# motherboard_conectors.net
KiCad netlist of a schematic drawn in Altium Designer
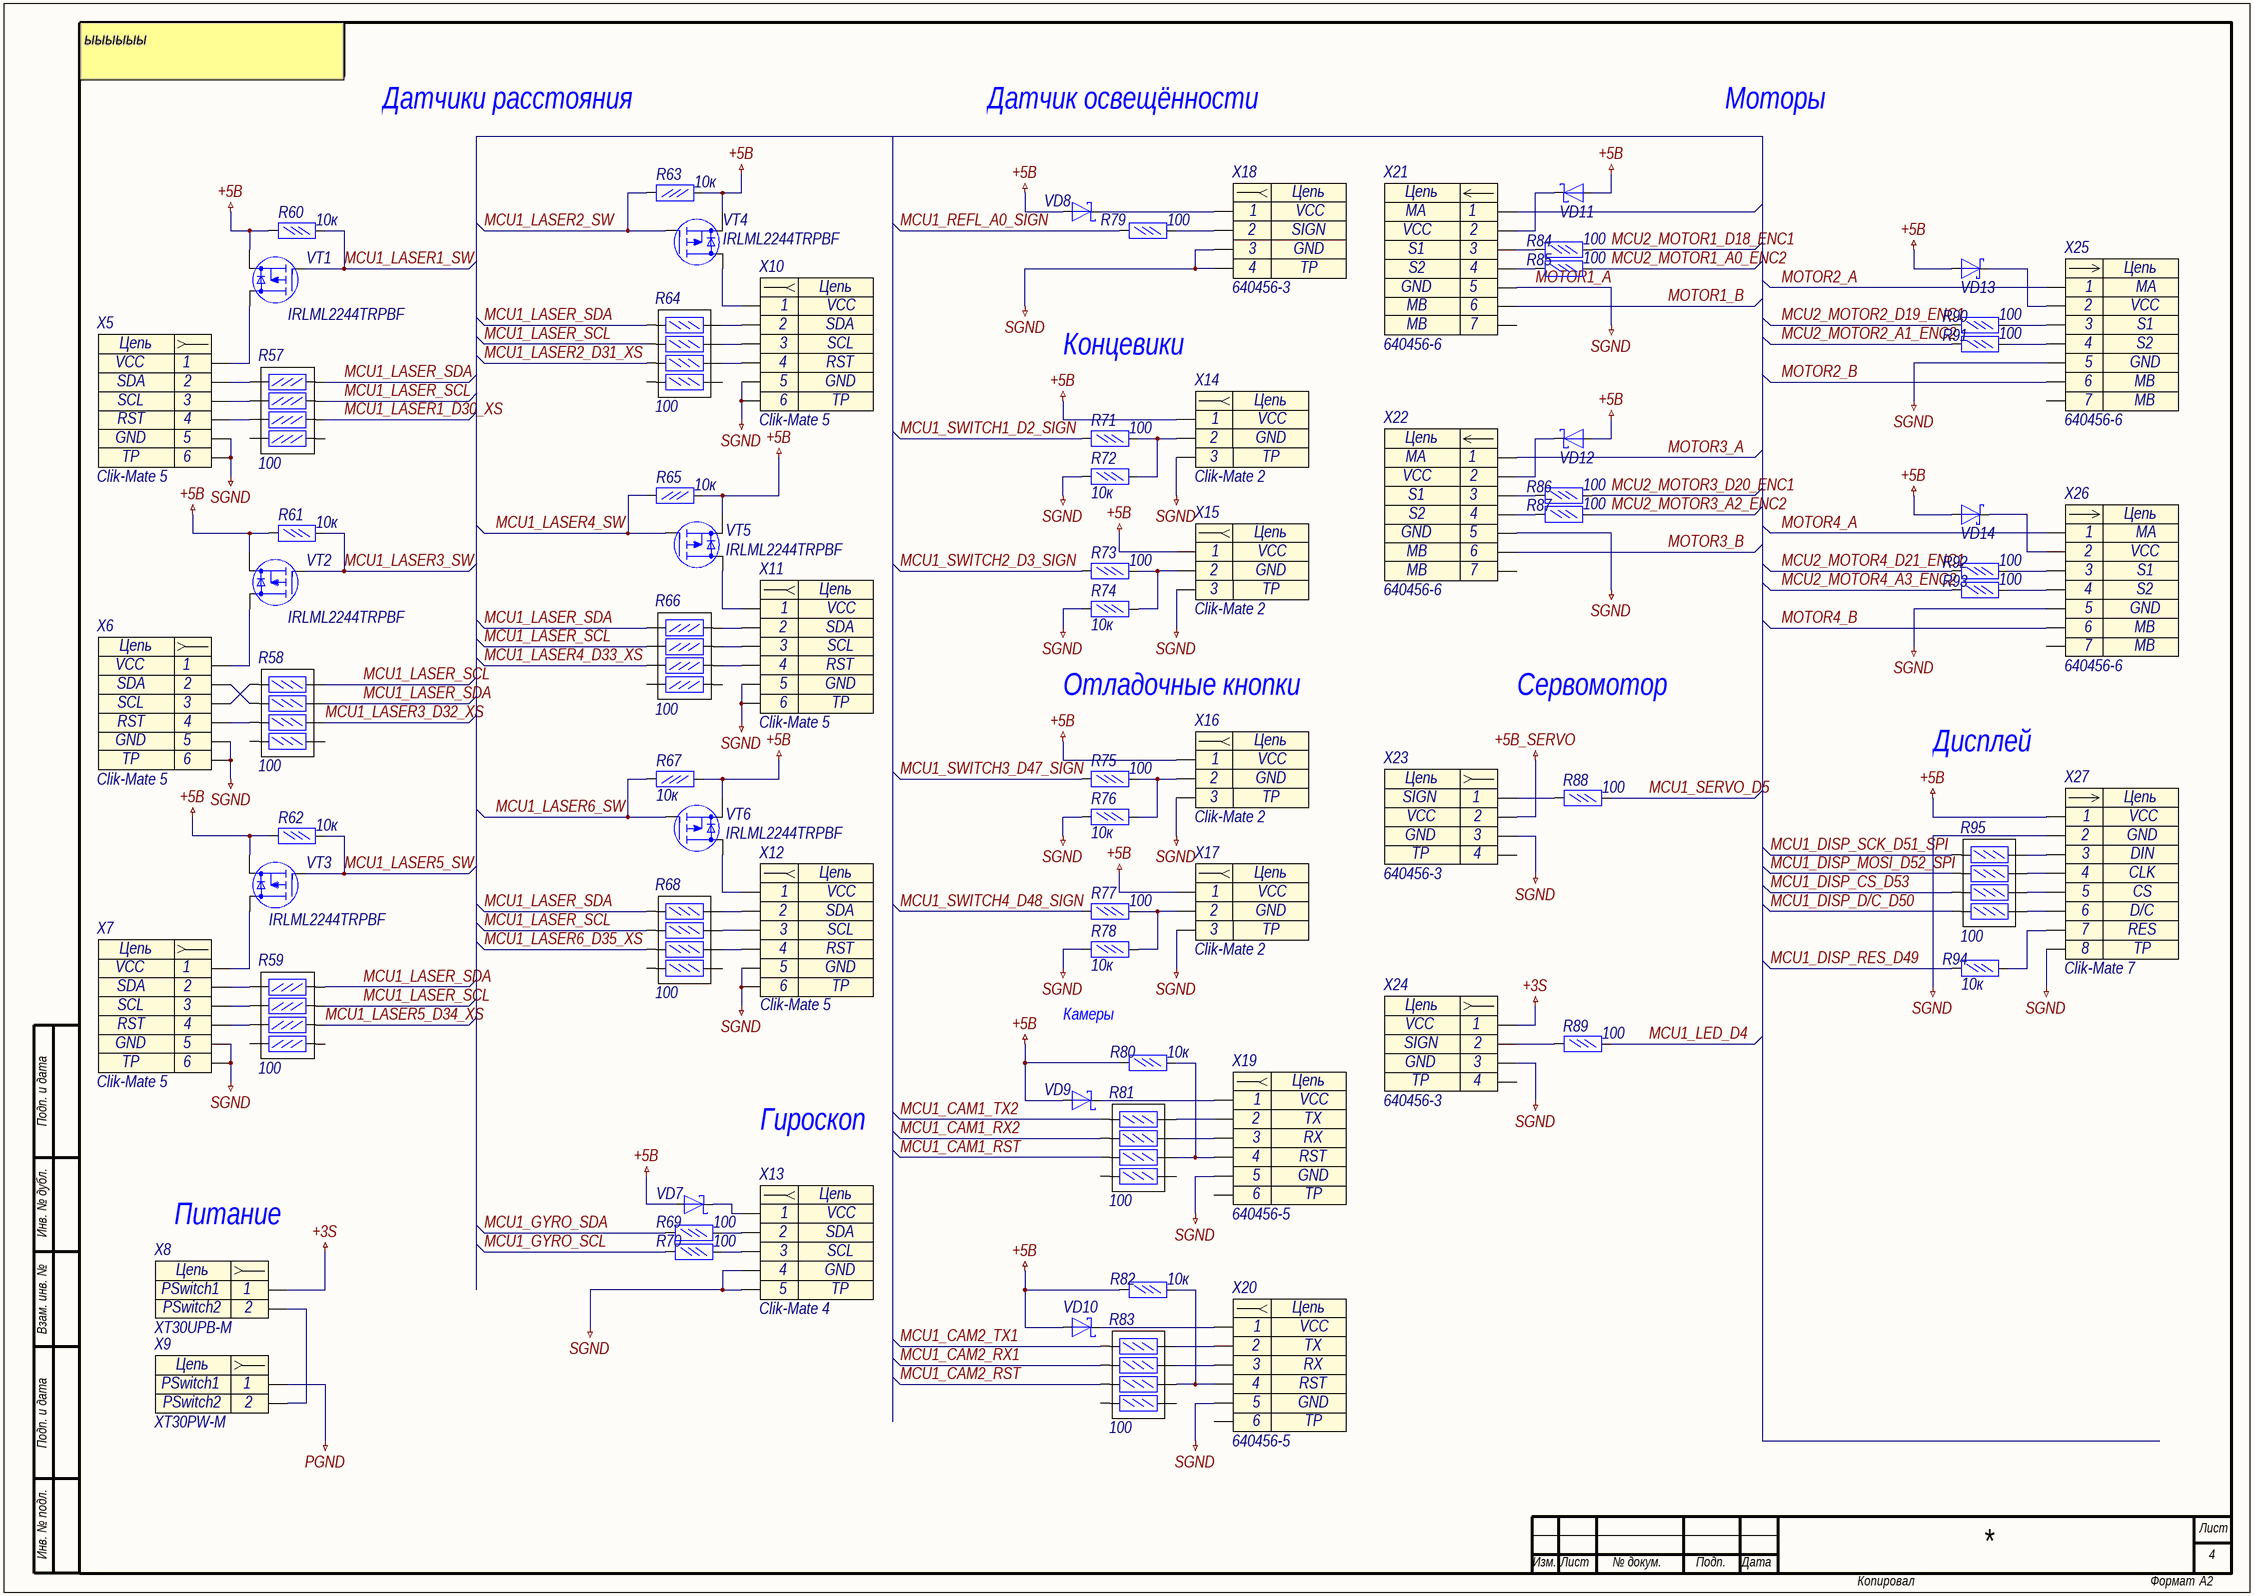
[diagram p0: motherboard_conectors.SchDoc]

(export (version "E")
  (design (tool "Eeschema 10.0.6"))
  (components
    (comp (ref "R57")
      (value "100")
      (footprint "R0603X4")
      (libsource (lib "") (part "Резисторная сборка 0.05 x 4_1"))
    )
    (comp (ref "R58")
      (value "100")
      (footprint "R0603X4")
      (libsource (lib "mylib") (part "Резисторная сборка 0.05 x 4"))
    )
    (comp (ref "R59")
      (value "100")
      (footprint "R0603X4")
      (libsource (lib "") (part "Резисторная сборка 0.05 x 4_1"))
    )
    (comp (ref "R60")
      (value "10к")
      (footprint "R0603")
      (description "Резистор 0,05Вт")
      (libsource (lib "mylib") (part "Резистор 0.05Вт"))
    )
    (comp (ref "R61")
      (value "10к")
      (footprint "R0603")
      (description "Резистор 0,05Вт")
      (libsource (lib "mylib") (part "Резистор 0.05Вт"))
    )
    (comp (ref "R62")
      (value "10к")
      (footprint "R0603")
      (description "Резистор 0,05Вт")
      (libsource (lib "mylib") (part "Резистор 0.05Вт"))
    )
    (comp (ref "R63")
      (value "10к")
      (footprint "R0603")
      (description "Резистор 0,05Вт")
      (libsource (lib "") (part "Резистор  0,05Вт_1"))
    )
    (comp (ref "R64")
      (value "100")
      (footprint "R0603X4")
      (libsource (lib "mylib") (part "Резисторная сборка 0.05 x 4"))
    )
    (comp (ref "R65")
      (value "10к")
      (footprint "R0603")
      (description "Резистор 0,05Вт")
      (libsource (lib "") (part "Резистор  0,05Вт_1"))
    )
    (comp (ref "R66")
      (value "100")
      (footprint "R0603X4")
      (libsource (lib "") (part "Резисторная сборка 0.05 x 4_1"))
    )
    (comp (ref "R67")
      (value "10к")
      (footprint "R0603")
      (description "Резистор 0,05Вт")
      (libsource (lib "") (part "Резистор  0,05Вт_1"))
    )
    (comp (ref "R68")
      (value "100")
      (footprint "R0603X4")
      (libsource (lib "mylib") (part "Резисторная сборка 0.05 x 4"))
    )
    (comp (ref "R69")
      (value "100")
      (footprint "R0603")
      (description "Резистор 0,05Вт")
      (libsource (lib "mylib") (part "Резистор 0.05Вт"))
    )
    (comp (ref "R70")
      (value "100")
      (footprint "R0603")
      (description "Резистор 0,05Вт")
      (libsource (lib "mylib") (part "Резистор 0.05Вт"))
    )
    (comp (ref "R71")
      (value "100")
      (footprint "R0603")
      (description "Резистор 0,05Вт")
      (libsource (lib "mylib") (part "Резистор  0,05Вт"))
    )
    (comp (ref "R72")
      (value "10к")
      (footprint "R0603")
      (description "Резистор 0,05Вт")
      (libsource (lib "mylib") (part "Резистор  0,05Вт"))
    )
    (comp (ref "R73")
      (value "100")
      (footprint "R0603")
      (description "Резистор 0,05Вт")
      (libsource (lib "mylib") (part "Резистор  0,05Вт"))
    )
    (comp (ref "R74")
      (value "10к")
      (footprint "R0603")
      (description "Резистор 0,05Вт")
      (libsource (lib "mylib") (part "Резистор  0,05Вт"))
    )
    (comp (ref "R75")
      (value "100")
      (footprint "R0603")
      (description "Резистор 0,05Вт")
      (libsource (lib "mylib") (part "Резистор  0,05Вт"))
    )
    (comp (ref "R76")
      (value "10к")
      (footprint "R0603")
      (description "Резистор 0,05Вт")
      (libsource (lib "mylib") (part "Резистор  0,05Вт"))
    )
    (comp (ref "R77")
      (value "100")
      (footprint "R0603")
      (description "Резистор 0,05Вт")
      (libsource (lib "mylib") (part "Резистор  0,05Вт"))
    )
    (comp (ref "R78")
      (value "10к")
      (footprint "R0603")
      (description "Резистор 0,05Вт")
      (libsource (lib "mylib") (part "Резистор  0,05Вт"))
    )
    (comp (ref "R79")
      (value "100")
      (footprint "R0603")
      (description "Резистор 0,05Вт")
      (libsource (lib "mylib") (part "Резистор  0,05Вт"))
    )
    (comp (ref "R80")
      (value "10к")
      (footprint "R0603")
      (description "Резистор 0,05Вт")
      (libsource (lib "mylib") (part "Резистор 0.05Вт"))
    )
    (comp (ref "R81")
      (value "100")
      (footprint "R0603X4")
      (libsource (lib "mylib") (part "Резисторная сборка 0.05 x 4"))
    )
    (comp (ref "R82")
      (value "10к")
      (footprint "R0603")
      (description "Резистор 0,05Вт")
      (libsource (lib "mylib") (part "Резистор 0.05Вт"))
    )
    (comp (ref "R83")
      (value "100")
      (footprint "R0603X4")
      (libsource (lib "mylib") (part "Резисторная сборка 0.05 x 4"))
    )
    (comp (ref "R84")
      (value "100")
      (footprint "R0603")
      (description "Резистор 0,05Вт")
      (libsource (lib "mylib") (part "Резистор  0,05Вт"))
    )
    (comp (ref "R85")
      (value "100")
      (footprint "R0603")
      (description "Резистор 0,05Вт")
      (libsource (lib "mylib") (part "Резистор  0,05Вт"))
    )
    (comp (ref "R86")
      (value "100")
      (footprint "R0603")
      (description "Резистор 0,05Вт")
      (libsource (lib "mylib") (part "Резистор  0,05Вт"))
    )
    (comp (ref "R87")
      (value "100")
      (footprint "R0603")
      (description "Резистор 0,05Вт")
      (libsource (lib "mylib") (part "Резистор  0,05Вт"))
    )
    (comp (ref "R88")
      (value "100")
      (footprint "R0603")
      (description "Резистор 0,05Вт")
      (libsource (lib "mylib") (part "Резистор  0,05Вт"))
    )
    (comp (ref "R89")
      (value "100")
      (footprint "R0603")
      (description "Резистор 0,05Вт")
      (libsource (lib "mylib") (part "Резистор  0,05Вт"))
    )
    (comp (ref "R90")
      (value "100")
      (footprint "R0603")
      (description "Резистор 0,05Вт")
      (libsource (lib "mylib") (part "Резистор  0,05Вт"))
    )
    (comp (ref "R91")
      (value "100")
      (footprint "R0603")
      (description "Резистор 0,05Вт")
      (libsource (lib "mylib") (part "Резистор  0,05Вт"))
    )
    (comp (ref "R92")
      (value "100")
      (footprint "R0603")
      (description "Резистор 0,05Вт")
      (libsource (lib "mylib") (part "Резистор  0,05Вт"))
    )
    (comp (ref "R93")
      (value "100")
      (footprint "R0603")
      (description "Резистор 0,05Вт")
      (libsource (lib "mylib") (part "Резистор  0,05Вт"))
    )
    (comp (ref "R94")
      (value "10к")
      (footprint "R0603")
      (description "Резистор 0,05Вт")
      (libsource (lib "mylib") (part "Резистор  0,05Вт"))
    )
    (comp (ref "R95")
      (value "100")
      (footprint "R0603X4")
      (libsource (lib "mylib") (part "Резисторная сборка 0.05 x 4"))
    )
    (comp (ref "VD7")
      (value "~")
      (footprint "SOD123_A")
      (description "Диод Шоттки")
      (libsource (lib "mylib") (part "DiodeSchottky"))
    )
    (comp (ref "VD8")
      (value "~")
      (footprint "SOD123_A")
      (description "Диод Шоттки")
      (libsource (lib "mylib") (part "DiodeSchottky"))
    )
    (comp (ref "VD9")
      (value "~")
      (footprint "SOD123_A")
      (description "Диод Шоттки")
      (libsource (lib "mylib") (part "DiodeSchottky"))
    )
    (comp (ref "VD10")
      (value "~")
      (footprint "SOD123_A")
      (description "Диод Шоттки")
      (libsource (lib "mylib") (part "DiodeSchottky"))
    )
    (comp (ref "VD11")
      (value "~")
      (footprint "SOD123_A")
      (description "Диод Шоттки")
      (libsource (lib "mylib") (part "DiodeSchottky"))
    )
    (comp (ref "VD12")
      (value "~")
      (footprint "SOD123_A")
      (description "Диод Шоттки")
      (libsource (lib "mylib") (part "DiodeSchottky"))
    )
    (comp (ref "VD13")
      (value "~")
      (footprint "SOD123_A")
      (description "Диод Шоттки")
      (libsource (lib "mylib") (part "DiodeSchottky"))
    )
    (comp (ref "VD14")
      (value "~")
      (footprint "SOD123_A")
      (description "Диод Шоттки")
      (libsource (lib "mylib") (part "DiodeSchottky"))
    )
    (comp (ref "VT1")
      (value "IRLML2244TRPBF")
      (footprint "SOT23")
      (libsource (lib "mylib") (part "транзистор n-канал"))
    )
    (comp (ref "VT2")
      (value "IRLML2244TRPBF")
      (footprint "SOT23")
      (libsource (lib "mylib") (part "транзистор n-канал"))
    )
    (comp (ref "VT3")
      (value "IRLML2244TRPBF")
      (footprint "SOT23")
      (libsource (lib "mylib") (part "транзистор n-канал"))
    )
    (comp (ref "VT4")
      (value "IRLML2244TRPBF")
      (footprint "SOT23")
      (libsource (lib "mylib") (part "транзистор n-канал"))
    )
    (comp (ref "VT5")
      (value "IRLML2244TRPBF")
      (footprint "SOT23")
      (libsource (lib "mylib") (part "транзистор n-канал"))
    )
    (comp (ref "VT6")
      (value "IRLML2244TRPBF")
      (footprint "SOT23")
      (libsource (lib "mylib") (part "транзистор n-канал"))
    )
    (comp (ref "X5")
      (value "Clik-Mate 5")
      (footprint "Clik-Mate 5")
      (description "Разъем - 5 конт. мама")
      (libsource (lib "") (part "Header_5_1"))
    )
    (comp (ref "X6")
      (value "Clik-Mate 5")
      (footprint "Clik-Mate 5")
      (description "Разъем - 5 конт. мама")
      (libsource (lib "") (part "Header_5_1"))
    )
    (comp (ref "X7")
      (value "Clik-Mate 5")
      (footprint "Clik-Mate 5")
      (description "Разъем - 5 конт. мама")
      (libsource (lib "") (part "Header_5_1"))
    )
    (comp (ref "X8") (value "XT30UPB-M") (footprint "XT30UPB-M") (libsource (lib "mylib") (part "XT30UPB-M")))
    (comp (ref "X9") (value "XT30PW-M") (footprint "XT30PW-M") (libsource (lib "mylib") (part "XT30PW-M")))
    (comp (ref "X10")
      (value "Clik-Mate 5")
      (footprint "Clik-Mate 5")
      (description "Разъем - 5 конт. мама")
      (libsource (lib "mylib") (part "Header_5"))
    )
    (comp (ref "X11")
      (value "Clik-Mate 5")
      (footprint "Clik-Mate 5")
      (description "Разъем - 5 конт. мама")
      (libsource (lib "mylib") (part "Header_5"))
    )
    (comp (ref "X12")
      (value "Clik-Mate 5")
      (footprint "Clik-Mate 5")
      (description "Разъем - 5 конт. мама")
      (libsource (lib "mylib") (part "Header_5"))
    )
    (comp (ref "X13")
      (value "Clik-Mate 4")
      (footprint "Clik-Mate 4")
      (description "Разъем - 4 конт. мама")
      (libsource (lib "mylib") (part "Header_4"))
    )
    (comp (ref "X14")
      (value "Clik-Mate 2")
      (footprint "Clik-Mate 2")
      (description "Разъем - 3 конт. розетка")
      (libsource (lib "mylib") (part "Header_2"))
    )
    (comp (ref "X15")
      (value "Clik-Mate 2")
      (footprint "Clik-Mate 2")
      (description "Разъем - 3 конт. розетка")
      (libsource (lib "mylib") (part "Header_2"))
    )
    (comp (ref "X16")
      (value "Clik-Mate 2")
      (footprint "Clik-Mate 2")
      (description "Разъем - 3 конт. розетка")
      (libsource (lib "mylib") (part "Header_2"))
    )
    (comp (ref "X17")
      (value "Clik-Mate 2")
      (footprint "Clik-Mate 2")
      (description "Разъем - 3 конт. розетка")
      (libsource (lib "mylib") (part "Header_2"))
    )
    (comp (ref "X18")
      (value "640456-3")
      (footprint "Clik-Mate 3")
      (description "Разъем - 3 конт. розетка")
      (libsource (lib "") (part "Header_3_1"))
    )
    (comp (ref "X19")
      (value "640456-5")
      (footprint "JST-640456-5")
      (description "Разъем - 5 конт. мама")
      (libsource (lib "mylib") (part "Header_5"))
    )
    (comp (ref "X20")
      (value "640456-5")
      (footprint "JST-640456-5")
      (description "Разъем - 5 конт. мама")
      (libsource (lib "mylib") (part "Header_5"))
    )
    (comp (ref "X21")
      (value "640456-6")
      (footprint "JST-640456-6")
      (description "Разъем - 6 конт. мама")
      (libsource (lib "") (part "Header_6_1"))
    )
    (comp (ref "X22")
      (value "640456-6")
      (footprint "JST-640456-6")
      (description "Разъем - 6 конт. мама")
      (libsource (lib "") (part "Header_6_1"))
    )
    (comp (ref "X23")
      (value "640456-3")
      (footprint "JST-640456-3")
      (description "Разъем - 3 конт. розетка")
      (libsource (lib "mylib") (part "Header_3"))
    )
    (comp (ref "X24")
      (value "640456-3")
      (footprint "JST-640456-3")
      (description "Разъем - 3 конт. розетка")
      (libsource (lib "mylib") (part "Header_3"))
    )
    (comp (ref "X25")
      (value "640456-6")
      (footprint "JST-640456-6")
      (description "Разъем - 6 конт. мама")
      (libsource (lib "mylib") (part "Header_6"))
    )
    (comp (ref "X26")
      (value "640456-6")
      (footprint "JST-640456-6")
      (description "Разъем - 6 конт. мама")
      (libsource (lib "mylib") (part "Header_6"))
    )
    (comp (ref "X27")
      (value "Clik-Mate 7")
      (footprint "Clik-Mate 7")
      (description "Разъем - 7 конт. мама")
      (libsource (lib "mylib") (part "Header_7"))
    )
  )
  (nets
    (net (code "1") (name "+3S") (class "Default")
      (node (ref "X24") (pin "1") (pinfunction "1_1") (pintype "passive"))
      (node (ref "X8") (pin "1") (pinfunction "1_1") (pintype "passive"))
    )
    (net (code "2") (name "+5В") (class "Default")
      (node (ref "R60") (pin "1") (pinfunction "1_1") (pintype "passive"))
      (node (ref "R61") (pin "1") (pinfunction "1_1") (pintype "passive"))
      (node (ref "R62") (pin "1") (pinfunction "1_1") (pintype "passive"))
      (node (ref "R63") (pin "1") (pinfunction "1_1") (pintype "passive"))
      (node (ref "R65") (pin "1") (pinfunction "1_1") (pintype "passive"))
      (node (ref "R67") (pin "1") (pinfunction "1_1") (pintype "passive"))
      (node (ref "R80") (pin "1") (pinfunction "1_1") (pintype "passive"))
      (node (ref "R82") (pin "1") (pinfunction "1_1") (pintype "passive"))
      (node (ref "VD10") (pin "2") (pinfunction "A_2") (pintype "passive"))
      (node (ref "VD11") (pin "2") (pinfunction "A_2") (pintype "passive"))
      (node (ref "VD12") (pin "2") (pinfunction "A_2") (pintype "passive"))
      (node (ref "VD13") (pin "2") (pinfunction "A_2") (pintype "passive"))
      (node (ref "VD14") (pin "2") (pinfunction "A_2") (pintype "passive"))
      (node (ref "VD7") (pin "2") (pinfunction "A_2") (pintype "passive"))
      (node (ref "VD8") (pin "2") (pinfunction "A_2") (pintype "passive"))
      (node (ref "VD9") (pin "2") (pinfunction "A_2") (pintype "passive"))
      (node (ref "VT1") (pin "2") (pinfunction "S_2") (pintype "passive"))
      (node (ref "VT2") (pin "2") (pinfunction "S_2") (pintype "passive"))
      (node (ref "VT3") (pin "2") (pinfunction "S_2") (pintype "passive"))
      (node (ref "VT4") (pin "2") (pinfunction "S_2") (pintype "passive"))
      (node (ref "VT5") (pin "2") (pinfunction "S_2") (pintype "passive"))
      (node (ref "VT6") (pin "2") (pinfunction "S_2") (pintype "passive"))
      (node (ref "X14") (pin "1") (pinfunction "1_1") (pintype "passive"))
      (node (ref "X15") (pin "1") (pinfunction "1_1") (pintype "passive"))
      (node (ref "X16") (pin "1") (pinfunction "1_1") (pintype "passive"))
      (node (ref "X17") (pin "1") (pinfunction "1_1") (pintype "passive"))
      (node (ref "X27") (pin "1") (pinfunction "1_1") (pintype "passive"))
    )
    (net (code "3") (name "+5В_SERVO") (class "Default")
      (node (ref "X23") (pin "2") (pinfunction "2_2") (pintype "passive"))
    )
    (net (code "4") (name "/MCU1_CAM1_RST") (class "Default")
      (node (ref "R81") (pin "5") (pinfunction "5_5") (pintype "passive"))
    )
    (net (code "5") (name "/MCU1_CAM1_RX2") (class "Default")
      (node (ref "R81") (pin "3") (pinfunction "3_3") (pintype "passive"))
    )
    (net (code "6") (name "/MCU1_CAM1_TX2") (class "Default")
      (node (ref "R81") (pin "1") (pinfunction "1_1") (pintype "passive"))
    )
    (net (code "7") (name "/MCU1_CAM2_RST") (class "Default")
      (node (ref "R83") (pin "5") (pinfunction "5_5") (pintype "passive"))
    )
    (net (code "8") (name "/MCU1_CAM2_RX1") (class "Default")
      (node (ref "R83") (pin "3") (pinfunction "3_3") (pintype "passive"))
    )
    (net (code "9") (name "/MCU1_CAM2_TX1") (class "Default")
      (node (ref "R83") (pin "1") (pinfunction "1_1") (pintype "passive"))
    )
    (net (code "10") (name "/MCU1_DISP_CS_D53") (class "Default")
      (node (ref "R95") (pin "5") (pinfunction "5_5") (pintype "passive"))
    )
    (net (code "11") (name "/MCU1_DISP_D{slash}C_D50") (class "Default")
      (node (ref "R95") (pin "7") (pinfunction "7_7") (pintype "passive"))
    )
    (net (code "12") (name "/MCU1_DISP_MOSI_D52_SPI") (class "Default")
      (node (ref "R95") (pin "3") (pinfunction "3_3") (pintype "passive"))
    )
    (net (code "13") (name "/MCU1_DISP_RES_D49") (class "Default")
      (node (ref "R94") (pin "1") (pinfunction "1_1") (pintype "passive"))
    )
    (net (code "14") (name "/MCU1_DISP_SCK_D51_SPI") (class "Default")
      (node (ref "R95") (pin "1") (pinfunction "1_1") (pintype "passive"))
    )
    (net (code "15") (name "/MCU1_GYRO_SCL") (class "Default")
      (node (ref "R70") (pin "1") (pinfunction "1_1") (pintype "passive"))
    )
    (net (code "16") (name "/MCU1_GYRO_SDA") (class "Default")
      (node (ref "R69") (pin "1") (pinfunction "1_1") (pintype "passive"))
    )
    (net (code "17") (name "/MCU1_LASER1_D30_XS") (class "Default")
      (node (ref "R57") (pin "5") (pinfunction "5_5") (pintype "passive"))
    )
    (net (code "18") (name "/MCU1_LASER1_SW") (class "Default")
      (node (ref "R60") (pin "2") (pinfunction "2_2") (pintype "passive"))
      (node (ref "VT1") (pin "1") (pinfunction "G_1") (pintype "passive"))
    )
    (net (code "19") (name "/MCU1_LASER2_D31_XS") (class "Default")
      (node (ref "R64") (pin "5") (pinfunction "5_5") (pintype "passive"))
    )
    (net (code "20") (name "/MCU1_LASER2_SW") (class "Default")
      (node (ref "R63") (pin "2") (pinfunction "2_2") (pintype "passive"))
      (node (ref "VT4") (pin "1") (pinfunction "G_1") (pintype "passive"))
    )
    (net (code "21") (name "/MCU1_LASER3_D32_XS") (class "Default")
      (node (ref "R58") (pin "6") (pinfunction "6_6") (pintype "passive"))
    )
    (net (code "22") (name "/MCU1_LASER3_SW") (class "Default")
      (node (ref "R61") (pin "2") (pinfunction "2_2") (pintype "passive"))
      (node (ref "VT2") (pin "1") (pinfunction "G_1") (pintype "passive"))
    )
    (net (code "23") (name "/MCU1_LASER4_D33_XS") (class "Default")
      (node (ref "R66") (pin "6") (pinfunction "6_6") (pintype "passive"))
    )
    (net (code "24") (name "/MCU1_LASER4_SW") (class "Default")
      (node (ref "R65") (pin "2") (pinfunction "2_2") (pintype "passive"))
      (node (ref "VT5") (pin "1") (pinfunction "G_1") (pintype "passive"))
    )
    (net (code "25") (name "/MCU1_LASER5_D34_XS") (class "Default")
      (node (ref "R59") (pin "5") (pinfunction "5_5") (pintype "passive"))
    )
    (net (code "26") (name "/MCU1_LASER5_SW") (class "Default")
      (node (ref "R62") (pin "2") (pinfunction "2_2") (pintype "passive"))
      (node (ref "VT3") (pin "1") (pinfunction "G_1") (pintype "passive"))
    )
    (net (code "27") (name "/MCU1_LASER6_D35_XS") (class "Default")
      (node (ref "R68") (pin "5") (pinfunction "5_5") (pintype "passive"))
    )
    (net (code "28") (name "/MCU1_LASER6_SW") (class "Default")
      (node (ref "R67") (pin "2") (pinfunction "2_2") (pintype "passive"))
      (node (ref "VT6") (pin "1") (pinfunction "G_1") (pintype "passive"))
    )
    (net (code "29") (name "/MCU1_LASER_SCL") (class "Default")
      (node (ref "R57") (pin "3") (pinfunction "3_3") (pintype "passive"))
      (node (ref "R58") (pin "2") (pinfunction "2_2") (pintype "passive"))
      (node (ref "R59") (pin "3") (pinfunction "3_3") (pintype "passive"))
      (node (ref "R64") (pin "3") (pinfunction "3_3") (pintype "passive"))
      (node (ref "R66") (pin "4") (pinfunction "4_4") (pintype "passive"))
      (node (ref "R68") (pin "3") (pinfunction "3_3") (pintype "passive"))
    )
    (net (code "30") (name "/MCU1_LASER_SDA") (class "Default")
      (node (ref "R57") (pin "1") (pinfunction "1_1") (pintype "passive"))
      (node (ref "R58") (pin "4") (pinfunction "4_4") (pintype "passive"))
      (node (ref "R59") (pin "1") (pinfunction "1_1") (pintype "passive"))
      (node (ref "R64") (pin "1") (pinfunction "1_1") (pintype "passive"))
      (node (ref "R66") (pin "2") (pinfunction "2_2") (pintype "passive"))
      (node (ref "R68") (pin "1") (pinfunction "1_1") (pintype "passive"))
    )
    (net (code "31") (name "/MCU1_LED_D4") (class "Default")
      (node (ref "R89") (pin "2") (pinfunction "2_2") (pintype "passive"))
    )
    (net (code "32") (name "/MCU1_REFL_A0_SIGN") (class "Default")
      (node (ref "R79") (pin "1") (pinfunction "1_1") (pintype "passive"))
    )
    (net (code "33") (name "/MCU1_SERVO_D5") (class "Default")
      (node (ref "R88") (pin "2") (pinfunction "2_2") (pintype "passive"))
    )
    (net (code "34") (name "/MCU1_SWITCH1_D2_SIGN") (class "Default")
      (node (ref "R71") (pin "1") (pinfunction "1_1") (pintype "passive"))
    )
    (net (code "35") (name "/MCU1_SWITCH2_D3_SIGN") (class "Default")
      (node (ref "R73") (pin "1") (pinfunction "1_1") (pintype "passive"))
    )
    (net (code "36") (name "/MCU1_SWITCH3_D47_SIGN") (class "Default")
      (node (ref "R75") (pin "1") (pinfunction "1_1") (pintype "passive"))
    )
    (net (code "37") (name "/MCU1_SWITCH4_D48_SIGN") (class "Default")
      (node (ref "R77") (pin "1") (pinfunction "1_1") (pintype "passive"))
    )
    (net (code "38") (name "/MCU2_MOTOR1_A0_ENC2") (class "Default")
      (node (ref "R85") (pin "2") (pinfunction "2_2") (pintype "passive"))
    )
    (net (code "39") (name "/MCU2_MOTOR1_D18_ENC1") (class "Default")
      (node (ref "R84") (pin "2") (pinfunction "2_2") (pintype "passive"))
    )
    (net (code "40") (name "/MCU2_MOTOR2_A1_ENC2") (class "Default")
      (node (ref "R91") (pin "1") (pinfunction "1_1") (pintype "passive"))
    )
    (net (code "41") (name "/MCU2_MOTOR2_D19_ENC1") (class "Default")
      (node (ref "R90") (pin "1") (pinfunction "1_1") (pintype "passive"))
    )
    (net (code "42") (name "/MCU2_MOTOR3_A2_ENC2") (class "Default")
      (node (ref "R87") (pin "2") (pinfunction "2_2") (pintype "passive"))
    )
    (net (code "43") (name "/MCU2_MOTOR3_D20_ENC1") (class "Default")
      (node (ref "R86") (pin "2") (pinfunction "2_2") (pintype "passive"))
    )
    (net (code "44") (name "/MCU2_MOTOR4_A3_ENC2") (class "Default")
      (node (ref "R93") (pin "1") (pinfunction "1_1") (pintype "passive"))
    )
    (net (code "45") (name "/MCU2_MOTOR4_D21_ENC1") (class "Default")
      (node (ref "R92") (pin "1") (pinfunction "1_1") (pintype "passive"))
    )
    (net (code "46") (name "/MOTOR1_B") (class "Default")
      (node (ref "X21") (pin "6") (pinfunction "6_6") (pintype "passive"))
    )
    (net (code "47") (name "/MOTOR2_A") (class "Default")
      (node (ref "X25") (pin "1") (pinfunction "1_1") (pintype "passive"))
    )
    (net (code "48") (name "/MOTOR2_B") (class "Default")
      (node (ref "X25") (pin "6") (pinfunction "6_6") (pintype "passive"))
    )
    (net (code "49") (name "/MOTOR3_A") (class "Default")
      (node (ref "X22") (pin "1") (pinfunction "1_1") (pintype "passive"))
    )
    (net (code "50") (name "/MOTOR3_B") (class "Default")
      (node (ref "X22") (pin "6") (pinfunction "6_6") (pintype "passive"))
    )
    (net (code "51") (name "/MOTOR4_A") (class "Default")
      (node (ref "X26") (pin "1") (pinfunction "1_1") (pintype "passive"))
    )
    (net (code "52") (name "/MOTOR4_B") (class "Default")
      (node (ref "X26") (pin "6") (pinfunction "6_6") (pintype "passive"))
    )
    (net (code "53") (name "Net-(R57-Pad2)") (class "Default")
      (node (ref "R57") (pin "2") (pinfunction "2_2") (pintype "passive"))
      (node (ref "X5") (pin "2") (pinfunction "2_2") (pintype "passive"))
    )
    (net (code "54") (name "Net-(R57-Pad4)") (class "Default")
      (node (ref "R57") (pin "4") (pinfunction "4_4") (pintype "passive"))
      (node (ref "X5") (pin "3") (pinfunction "3_3") (pintype "passive"))
    )
    (net (code "55") (name "Net-(R57-Pad6)") (class "Default")
      (node (ref "R57") (pin "6") (pinfunction "6_6") (pintype "passive"))
      (node (ref "X5") (pin "4") (pinfunction "4_4") (pintype "passive"))
    )
    (net (code "56") (name "Net-(R58-Pad1)") (class "Default")
      (node (ref "R58") (pin "1") (pinfunction "1_1") (pintype "passive"))
      (node (ref "X6") (pin "3") (pinfunction "3_3") (pintype "passive"))
    )
    (net (code "57") (name "Net-(R58-Pad3)") (class "Default")
      (node (ref "R58") (pin "3") (pinfunction "3_3") (pintype "passive"))
      (node (ref "X6") (pin "2") (pinfunction "2_2") (pintype "passive"))
    )
    (net (code "58") (name "Net-(R58-Pad5)") (class "Default")
      (node (ref "R58") (pin "5") (pinfunction "5_5") (pintype "passive"))
      (node (ref "X6") (pin "4") (pinfunction "4_4") (pintype "passive"))
    )
    (net (code "59") (name "Net-(R59-Pad2)") (class "Default")
      (node (ref "R59") (pin "2") (pinfunction "2_2") (pintype "passive"))
      (node (ref "X7") (pin "2") (pinfunction "2_2") (pintype "passive"))
    )
    (net (code "60") (name "Net-(R59-Pad4)") (class "Default")
      (node (ref "R59") (pin "4") (pinfunction "4_4") (pintype "passive"))
      (node (ref "X7") (pin "3") (pinfunction "3_3") (pintype "passive"))
    )
    (net (code "61") (name "Net-(R59-Pad6)") (class "Default")
      (node (ref "R59") (pin "6") (pinfunction "6_6") (pintype "passive"))
      (node (ref "X7") (pin "4") (pinfunction "4_4") (pintype "passive"))
    )
    (net (code "62") (name "Net-(R64-Pad2)") (class "Default")
      (node (ref "R64") (pin "2") (pinfunction "2_2") (pintype "passive"))
      (node (ref "X10") (pin "2") (pinfunction "2_2") (pintype "passive"))
    )
    (net (code "63") (name "Net-(R64-Pad4)") (class "Default")
      (node (ref "R64") (pin "4") (pinfunction "4_4") (pintype "passive"))
      (node (ref "X10") (pin "3") (pinfunction "3_3") (pintype "passive"))
    )
    (net (code "64") (name "Net-(R64-Pad6)") (class "Default")
      (node (ref "R64") (pin "6") (pinfunction "6_6") (pintype "passive"))
      (node (ref "X10") (pin "4") (pinfunction "4_4") (pintype "passive"))
    )
    (net (code "65") (name "Net-(R66-Pad1)") (class "Default")
      (node (ref "R66") (pin "1") (pinfunction "1_1") (pintype "passive"))
      (node (ref "X11") (pin "2") (pinfunction "2_2") (pintype "passive"))
    )
    (net (code "66") (name "Net-(R66-Pad3)") (class "Default")
      (node (ref "R66") (pin "3") (pinfunction "3_3") (pintype "passive"))
      (node (ref "X11") (pin "3") (pinfunction "3_3") (pintype "passive"))
    )
    (net (code "67") (name "Net-(R66-Pad5)") (class "Default")
      (node (ref "R66") (pin "5") (pinfunction "5_5") (pintype "passive"))
      (node (ref "X11") (pin "4") (pinfunction "4_4") (pintype "passive"))
    )
    (net (code "68") (name "Net-(R68-Pad2)") (class "Default")
      (node (ref "R68") (pin "2") (pinfunction "2_2") (pintype "passive"))
      (node (ref "X12") (pin "2") (pinfunction "2_2") (pintype "passive"))
    )
    (net (code "69") (name "Net-(R68-Pad4)") (class "Default")
      (node (ref "R68") (pin "4") (pinfunction "4_4") (pintype "passive"))
      (node (ref "X12") (pin "3") (pinfunction "3_3") (pintype "passive"))
    )
    (net (code "70") (name "Net-(R68-Pad6)") (class "Default")
      (node (ref "R68") (pin "6") (pinfunction "6_6") (pintype "passive"))
      (node (ref "X12") (pin "4") (pinfunction "4_4") (pintype "passive"))
    )
    (net (code "71") (name "Net-(R69-Pad2)") (class "Default")
      (node (ref "R69") (pin "2") (pinfunction "2_2") (pintype "passive"))
      (node (ref "X13") (pin "2") (pinfunction "2_2") (pintype "passive"))
    )
    (net (code "72") (name "Net-(R70-Pad2)") (class "Default")
      (node (ref "R70") (pin "2") (pinfunction "2_2") (pintype "passive"))
      (node (ref "X13") (pin "3") (pinfunction "3_3") (pintype "passive"))
    )
    (net (code "73") (name "Net-(R71-Pad2)") (class "Default")
      (node (ref "R71") (pin "2") (pinfunction "2_2") (pintype "passive"))
      (node (ref "R72") (pin "2") (pinfunction "2_2") (pintype "passive"))
      (node (ref "X14") (pin "2") (pinfunction "2_2") (pintype "passive"))
    )
    (net (code "74") (name "Net-(R73-Pad2)") (class "Default")
      (node (ref "R73") (pin "2") (pinfunction "2_2") (pintype "passive"))
      (node (ref "R74") (pin "2") (pinfunction "2_2") (pintype "passive"))
      (node (ref "X15") (pin "2") (pinfunction "2_2") (pintype "passive"))
    )
    (net (code "75") (name "Net-(R75-Pad2)") (class "Default")
      (node (ref "R75") (pin "2") (pinfunction "2_2") (pintype "passive"))
      (node (ref "R76") (pin "2") (pinfunction "2_2") (pintype "passive"))
      (node (ref "X16") (pin "2") (pinfunction "2_2") (pintype "passive"))
    )
    (net (code "76") (name "Net-(R77-Pad2)") (class "Default")
      (node (ref "R77") (pin "2") (pinfunction "2_2") (pintype "passive"))
      (node (ref "R78") (pin "2") (pinfunction "2_2") (pintype "passive"))
      (node (ref "X17") (pin "2") (pinfunction "2_2") (pintype "passive"))
    )
    (net (code "77") (name "Net-(R79-Pad2)") (class "Default")
      (node (ref "R79") (pin "2") (pinfunction "2_2") (pintype "passive"))
      (node (ref "X18") (pin "2") (pinfunction "2_2") (pintype "passive"))
    )
    (net (code "78") (name "Net-(R80-Pad2)") (class "Default")
      (node (ref "R80") (pin "2") (pinfunction "2_2") (pintype "passive"))
      (node (ref "R81") (pin "6") (pinfunction "6_6") (pintype "passive"))
      (node (ref "X19") (pin "4") (pinfunction "4_4") (pintype "passive"))
    )
    (net (code "79") (name "Net-(R81-Pad2)") (class "Default")
      (node (ref "R81") (pin "2") (pinfunction "2_2") (pintype "passive"))
      (node (ref "X19") (pin "2") (pinfunction "2_2") (pintype "passive"))
    )
    (net (code "80") (name "Net-(R81-Pad4)") (class "Default")
      (node (ref "R81") (pin "4") (pinfunction "4_4") (pintype "passive"))
      (node (ref "X19") (pin "3") (pinfunction "3_3") (pintype "passive"))
    )
    (net (code "81") (name "Net-(R82-Pad2)") (class "Default")
      (node (ref "R82") (pin "2") (pinfunction "2_2") (pintype "passive"))
      (node (ref "R83") (pin "6") (pinfunction "6_6") (pintype "passive"))
      (node (ref "X20") (pin "4") (pinfunction "4_4") (pintype "passive"))
    )
    (net (code "82") (name "Net-(R83-Pad2)") (class "Default")
      (node (ref "R83") (pin "2") (pinfunction "2_2") (pintype "passive"))
      (node (ref "X20") (pin "2") (pinfunction "2_2") (pintype "passive"))
    )
    (net (code "83") (name "Net-(R83-Pad4)") (class "Default")
      (node (ref "R83") (pin "4") (pinfunction "4_4") (pintype "passive"))
      (node (ref "X20") (pin "3") (pinfunction "3_3") (pintype "passive"))
    )
    (net (code "84") (name "Net-(R84-Pad1)") (class "Default")
      (node (ref "R84") (pin "1") (pinfunction "1_1") (pintype "passive"))
      (node (ref "X21") (pin "3") (pinfunction "3_3") (pintype "passive"))
    )
    (net (code "85") (name "Net-(R85-Pad1)") (class "Default")
      (node (ref "R85") (pin "1") (pinfunction "1_1") (pintype "passive"))
      (node (ref "X21") (pin "4") (pinfunction "4_4") (pintype "passive"))
    )
    (net (code "86") (name "Net-(R86-Pad1)") (class "Default")
      (node (ref "R86") (pin "1") (pinfunction "1_1") (pintype "passive"))
      (node (ref "X22") (pin "3") (pinfunction "3_3") (pintype "passive"))
    )
    (net (code "87") (name "Net-(R87-Pad1)") (class "Default")
      (node (ref "R87") (pin "1") (pinfunction "1_1") (pintype "passive"))
      (node (ref "X22") (pin "4") (pinfunction "4_4") (pintype "passive"))
    )
    (net (code "88") (name "Net-(R88-Pad1)") (class "Default")
      (node (ref "R88") (pin "1") (pinfunction "1_1") (pintype "passive"))
      (node (ref "X23") (pin "1") (pinfunction "1_1") (pintype "passive"))
    )
    (net (code "89") (name "Net-(R89-Pad1)") (class "Default")
      (node (ref "R89") (pin "1") (pinfunction "1_1") (pintype "passive"))
      (node (ref "X24") (pin "2") (pinfunction "2_2") (pintype "passive"))
    )
    (net (code "90") (name "Net-(R90-Pad2)") (class "Default")
      (node (ref "R90") (pin "2") (pinfunction "2_2") (pintype "passive"))
      (node (ref "X25") (pin "3") (pinfunction "3_3") (pintype "passive"))
    )
    (net (code "91") (name "Net-(R91-Pad2)") (class "Default")
      (node (ref "R91") (pin "2") (pinfunction "2_2") (pintype "passive"))
      (node (ref "X25") (pin "4") (pinfunction "4_4") (pintype "passive"))
    )
    (net (code "92") (name "Net-(R92-Pad2)") (class "Default")
      (node (ref "R92") (pin "2") (pinfunction "2_2") (pintype "passive"))
      (node (ref "X26") (pin "3") (pinfunction "3_3") (pintype "passive"))
    )
    (net (code "93") (name "Net-(R93-Pad2)") (class "Default")
      (node (ref "R93") (pin "2") (pinfunction "2_2") (pintype "passive"))
      (node (ref "X26") (pin "4") (pinfunction "4_4") (pintype "passive"))
    )
    (net (code "94") (name "Net-(R94-Pad2)") (class "Default")
      (node (ref "R94") (pin "2") (pinfunction "2_2") (pintype "passive"))
      (node (ref "X27") (pin "7") (pinfunction "7_7") (pintype "passive"))
    )
    (net (code "95") (name "Net-(R95-Pad2)") (class "Default")
      (node (ref "R95") (pin "2") (pinfunction "2_2") (pintype "passive"))
      (node (ref "X27") (pin "3") (pinfunction "3_3") (pintype "passive"))
    )
    (net (code "96") (name "Net-(R95-Pad4)") (class "Default")
      (node (ref "R95") (pin "4") (pinfunction "4_4") (pintype "passive"))
      (node (ref "X27") (pin "4") (pinfunction "4_4") (pintype "passive"))
    )
    (net (code "97") (name "Net-(R95-Pad6)") (class "Default")
      (node (ref "R95") (pin "6") (pinfunction "6_6") (pintype "passive"))
      (node (ref "X27") (pin "5") (pinfunction "5_5") (pintype "passive"))
    )
    (net (code "98") (name "Net-(R95-Pad8)") (class "Default")
      (node (ref "R95") (pin "8") (pinfunction "8_8") (pintype "passive"))
      (node (ref "X27") (pin "6") (pinfunction "6_6") (pintype "passive"))
    )
    (net (code "99") (name "Net-(VD7-K)") (class "Default")
      (node (ref "VD7") (pin "1") (pinfunction "K_1") (pintype "passive"))
      (node (ref "X13") (pin "1") (pinfunction "1_1") (pintype "passive"))
    )
    (net (code "100") (name "Net-(VD8-K)") (class "Default")
      (node (ref "VD8") (pin "1") (pinfunction "K_1") (pintype "passive"))
      (node (ref "X18") (pin "1") (pinfunction "1_1") (pintype "passive"))
    )
    (net (code "101") (name "Net-(VD9-K)") (class "Default")
      (node (ref "VD9") (pin "1") (pinfunction "K_1") (pintype "passive"))
      (node (ref "X19") (pin "1") (pinfunction "1_1") (pintype "passive"))
    )
    (net (code "102") (name "Net-(VD10-K)") (class "Default")
      (node (ref "VD10") (pin "1") (pinfunction "K_1") (pintype "passive"))
      (node (ref "X20") (pin "1") (pinfunction "1_1") (pintype "passive"))
    )
    (net (code "103") (name "Net-(VD11-K)") (class "Default")
      (node (ref "VD11") (pin "1") (pinfunction "K_1") (pintype "passive"))
      (node (ref "X21") (pin "2") (pinfunction "2_2") (pintype "passive"))
    )
    (net (code "104") (name "Net-(VD12-K)") (class "Default")
      (node (ref "VD12") (pin "1") (pinfunction "K_1") (pintype "passive"))
      (node (ref "X22") (pin "2") (pinfunction "2_2") (pintype "passive"))
    )
    (net (code "105") (name "Net-(VD13-K)") (class "Default")
      (node (ref "VD13") (pin "1") (pinfunction "K_1") (pintype "passive"))
      (node (ref "X25") (pin "2") (pinfunction "2_2") (pintype "passive"))
    )
    (net (code "106") (name "Net-(VD14-K)") (class "Default")
      (node (ref "VD14") (pin "1") (pinfunction "K_1") (pintype "passive"))
      (node (ref "X26") (pin "2") (pinfunction "2_2") (pintype "passive"))
    )
    (net (code "107") (name "Net-(VT1-D)") (class "Default")
      (node (ref "VT1") (pin "3") (pinfunction "D_3") (pintype "passive"))
      (node (ref "X5") (pin "1") (pinfunction "1_1") (pintype "passive"))
    )
    (net (code "108") (name "Net-(VT2-D)") (class "Default")
      (node (ref "VT2") (pin "3") (pinfunction "D_3") (pintype "passive"))
      (node (ref "X6") (pin "1") (pinfunction "1_1") (pintype "passive"))
    )
    (net (code "109") (name "Net-(VT3-D)") (class "Default")
      (node (ref "VT3") (pin "3") (pinfunction "D_3") (pintype "passive"))
      (node (ref "X7") (pin "1") (pinfunction "1_1") (pintype "passive"))
    )
    (net (code "110") (name "Net-(VT4-D)") (class "Default")
      (node (ref "VT4") (pin "3") (pinfunction "D_3") (pintype "passive"))
      (node (ref "X10") (pin "1") (pinfunction "1_1") (pintype "passive"))
    )
    (net (code "111") (name "Net-(VT5-D)") (class "Default")
      (node (ref "VT5") (pin "3") (pinfunction "D_3") (pintype "passive"))
      (node (ref "X11") (pin "1") (pinfunction "1_1") (pintype "passive"))
    )
    (net (code "112") (name "Net-(VT6-D)") (class "Default")
      (node (ref "VT6") (pin "3") (pinfunction "D_3") (pintype "passive"))
      (node (ref "X12") (pin "1") (pinfunction "1_1") (pintype "passive"))
    )
    (net (code "113") (name "Net-(X8-Pad2)") (class "Default")
      (node (ref "X8") (pin "2") (pinfunction "2_2") (pintype "passive"))
      (node (ref "X9") (pin "2") (pinfunction "2_2") (pintype "passive"))
    )
    (net (code "114") (name "PGND") (class "Default")
      (node (ref "X9") (pin "1") (pinfunction "1_1") (pintype "passive"))
    )
    (net (code "115") (name "SGND") (class "Default")
      (node (ref "R72") (pin "1") (pinfunction "1_1") (pintype "passive"))
      (node (ref "R74") (pin "1") (pinfunction "1_1") (pintype "passive"))
      (node (ref "R76") (pin "1") (pinfunction "1_1") (pintype "passive"))
      (node (ref "R78") (pin "1") (pinfunction "1_1") (pintype "passive"))
      (node (ref "X10") (pin "0") (pinfunction "0_0") (pintype "passive"))
      (node (ref "X10") (pin "5") (pinfunction "5_5") (pintype "passive"))
      (node (ref "X11") (pin "0") (pinfunction "0_0") (pintype "passive"))
      (node (ref "X11") (pin "5") (pinfunction "5_5") (pintype "passive"))
      (node (ref "X12") (pin "0") (pinfunction "0_0") (pintype "passive"))
      (node (ref "X12") (pin "5") (pinfunction "5_5") (pintype "passive"))
      (node (ref "X13") (pin "0") (pinfunction "0_0") (pintype "passive"))
      (node (ref "X13") (pin "4") (pinfunction "4_4") (pintype "passive"))
      (node (ref "X14") (pin "0") (pinfunction "0_0") (pintype "passive"))
      (node (ref "X15") (pin "0") (pinfunction "0_0") (pintype "passive"))
      (node (ref "X16") (pin "0") (pinfunction "0_0") (pintype "passive"))
      (node (ref "X17") (pin "0") (pinfunction "0_0") (pintype "passive"))
      (node (ref "X18") (pin "0") (pinfunction "0_0") (pintype "passive"))
      (node (ref "X18") (pin "3") (pinfunction "3_3") (pintype "passive"))
      (node (ref "X19") (pin "5") (pinfunction "5_5") (pintype "passive"))
      (node (ref "X20") (pin "5") (pinfunction "5_5") (pintype "passive"))
      (node (ref "X21") (pin "5") (pinfunction "5_5") (pintype "passive"))
      (node (ref "X22") (pin "5") (pinfunction "5_5") (pintype "passive"))
      (node (ref "X23") (pin "3") (pinfunction "3_3") (pintype "passive"))
      (node (ref "X24") (pin "3") (pinfunction "3_3") (pintype "passive"))
      (node (ref "X25") (pin "5") (pinfunction "5_5") (pintype "passive"))
      (node (ref "X26") (pin "5") (pinfunction "5_5") (pintype "passive"))
      (node (ref "X27") (pin "0") (pinfunction "0_0") (pintype "passive"))
      (node (ref "X27") (pin "2") (pinfunction "2_2") (pintype "passive"))
      (node (ref "X5") (pin "0") (pinfunction "0_0") (pintype "passive"))
      (node (ref "X5") (pin "5") (pinfunction "5_5") (pintype "passive"))
      (node (ref "X6") (pin "0") (pinfunction "0_0") (pintype "passive"))
      (node (ref "X6") (pin "5") (pinfunction "5_5") (pintype "passive"))
      (node (ref "X7") (pin "0") (pinfunction "0_0") (pintype "passive"))
      (node (ref "X7") (pin "5") (pinfunction "5_5") (pintype "passive"))
    )
    (net (code "116") (name "unconnected-(R57-Pad7)") (class "Default")
      (node (ref "R57") (pin "7") (pinfunction "7_7") (pintype "passive"))
    )
    (net (code "117") (name "unconnected-(R57-Pad8)") (class "Default")
      (node (ref "R57") (pin "8") (pinfunction "8_8") (pintype "passive"))
    )
    (net (code "118") (name "unconnected-(R58-Pad7)") (class "Default")
      (node (ref "R58") (pin "7") (pinfunction "7_7") (pintype "passive"))
    )
    (net (code "119") (name "unconnected-(R58-Pad8)") (class "Default")
      (node (ref "R58") (pin "8") (pinfunction "8_8") (pintype "passive"))
    )
    (net (code "120") (name "unconnected-(R59-Pad7)") (class "Default")
      (node (ref "R59") (pin "7") (pinfunction "7_7") (pintype "passive"))
    )
    (net (code "121") (name "unconnected-(R59-Pad8)") (class "Default")
      (node (ref "R59") (pin "8") (pinfunction "8_8") (pintype "passive"))
    )
    (net (code "122") (name "unconnected-(R64-Pad7)") (class "Default")
      (node (ref "R64") (pin "7") (pinfunction "7_7") (pintype "passive"))
    )
    (net (code "123") (name "unconnected-(R64-Pad8)") (class "Default")
      (node (ref "R64") (pin "8") (pinfunction "8_8") (pintype "passive"))
    )
    (net (code "124") (name "unconnected-(R66-Pad7)") (class "Default")
      (node (ref "R66") (pin "7") (pinfunction "7_7") (pintype "passive"))
    )
    (net (code "125") (name "unconnected-(R66-Pad8)") (class "Default")
      (node (ref "R66") (pin "8") (pinfunction "8_8") (pintype "passive"))
    )
    (net (code "126") (name "unconnected-(R68-Pad7)") (class "Default")
      (node (ref "R68") (pin "7") (pinfunction "7_7") (pintype "passive"))
    )
    (net (code "127") (name "unconnected-(R68-Pad8)") (class "Default")
      (node (ref "R68") (pin "8") (pinfunction "8_8") (pintype "passive"))
    )
    (net (code "128") (name "unconnected-(R81-Pad7)") (class "Default")
      (node (ref "R81") (pin "7") (pinfunction "7_7") (pintype "passive"))
    )
    (net (code "129") (name "unconnected-(R81-Pad8)") (class "Default")
      (node (ref "R81") (pin "8") (pinfunction "8_8") (pintype "passive"))
    )
    (net (code "130") (name "unconnected-(R83-Pad7)") (class "Default")
      (node (ref "R83") (pin "7") (pinfunction "7_7") (pintype "passive"))
    )
    (net (code "131") (name "unconnected-(R83-Pad8)") (class "Default")
      (node (ref "R83") (pin "8") (pinfunction "8_8") (pintype "passive"))
    )
    (net (code "132") (name "unconnected-(X19-Pad0)") (class "Default")
      (node (ref "X19") (pin "0") (pinfunction "0_0") (pintype "passive"))
    )
    (net (code "133") (name "unconnected-(X20-Pad0)") (class "Default")
      (node (ref "X20") (pin "0") (pinfunction "0_0") (pintype "passive"))
    )
    (net (code "134") (name "unconnected-(X21-Pad0)") (class "Default")
      (node (ref "X21") (pin "0") (pinfunction "0_0") (pintype "passive"))
    )
    (net (code "135") (name "unconnected-(X21-Pad1)") (class "Default")
      (node (ref "X21") (pin "1") (pinfunction "1_1") (pintype "passive"))
    )
    (net (code "136") (name "unconnected-(X22-Pad0)") (class "Default")
      (node (ref "X22") (pin "0") (pinfunction "0_0") (pintype "passive"))
    )
    (net (code "137") (name "unconnected-(X23-Pad0)") (class "Default")
      (node (ref "X23") (pin "0") (pinfunction "0_0") (pintype "passive"))
    )
    (net (code "138") (name "unconnected-(X24-Pad0)") (class "Default")
      (node (ref "X24") (pin "0") (pinfunction "0_0") (pintype "passive"))
    )
    (net (code "139") (name "unconnected-(X25-Pad0)") (class "Default")
      (node (ref "X25") (pin "0") (pinfunction "0_0") (pintype "passive"))
    )
    (net (code "140") (name "unconnected-(X26-Pad0)") (class "Default")
      (node (ref "X26") (pin "0") (pinfunction "0_0") (pintype "passive"))
    )
  )
)
